# mezzanine.net
KiCad netlist of a schematic drawn in Altium Designer
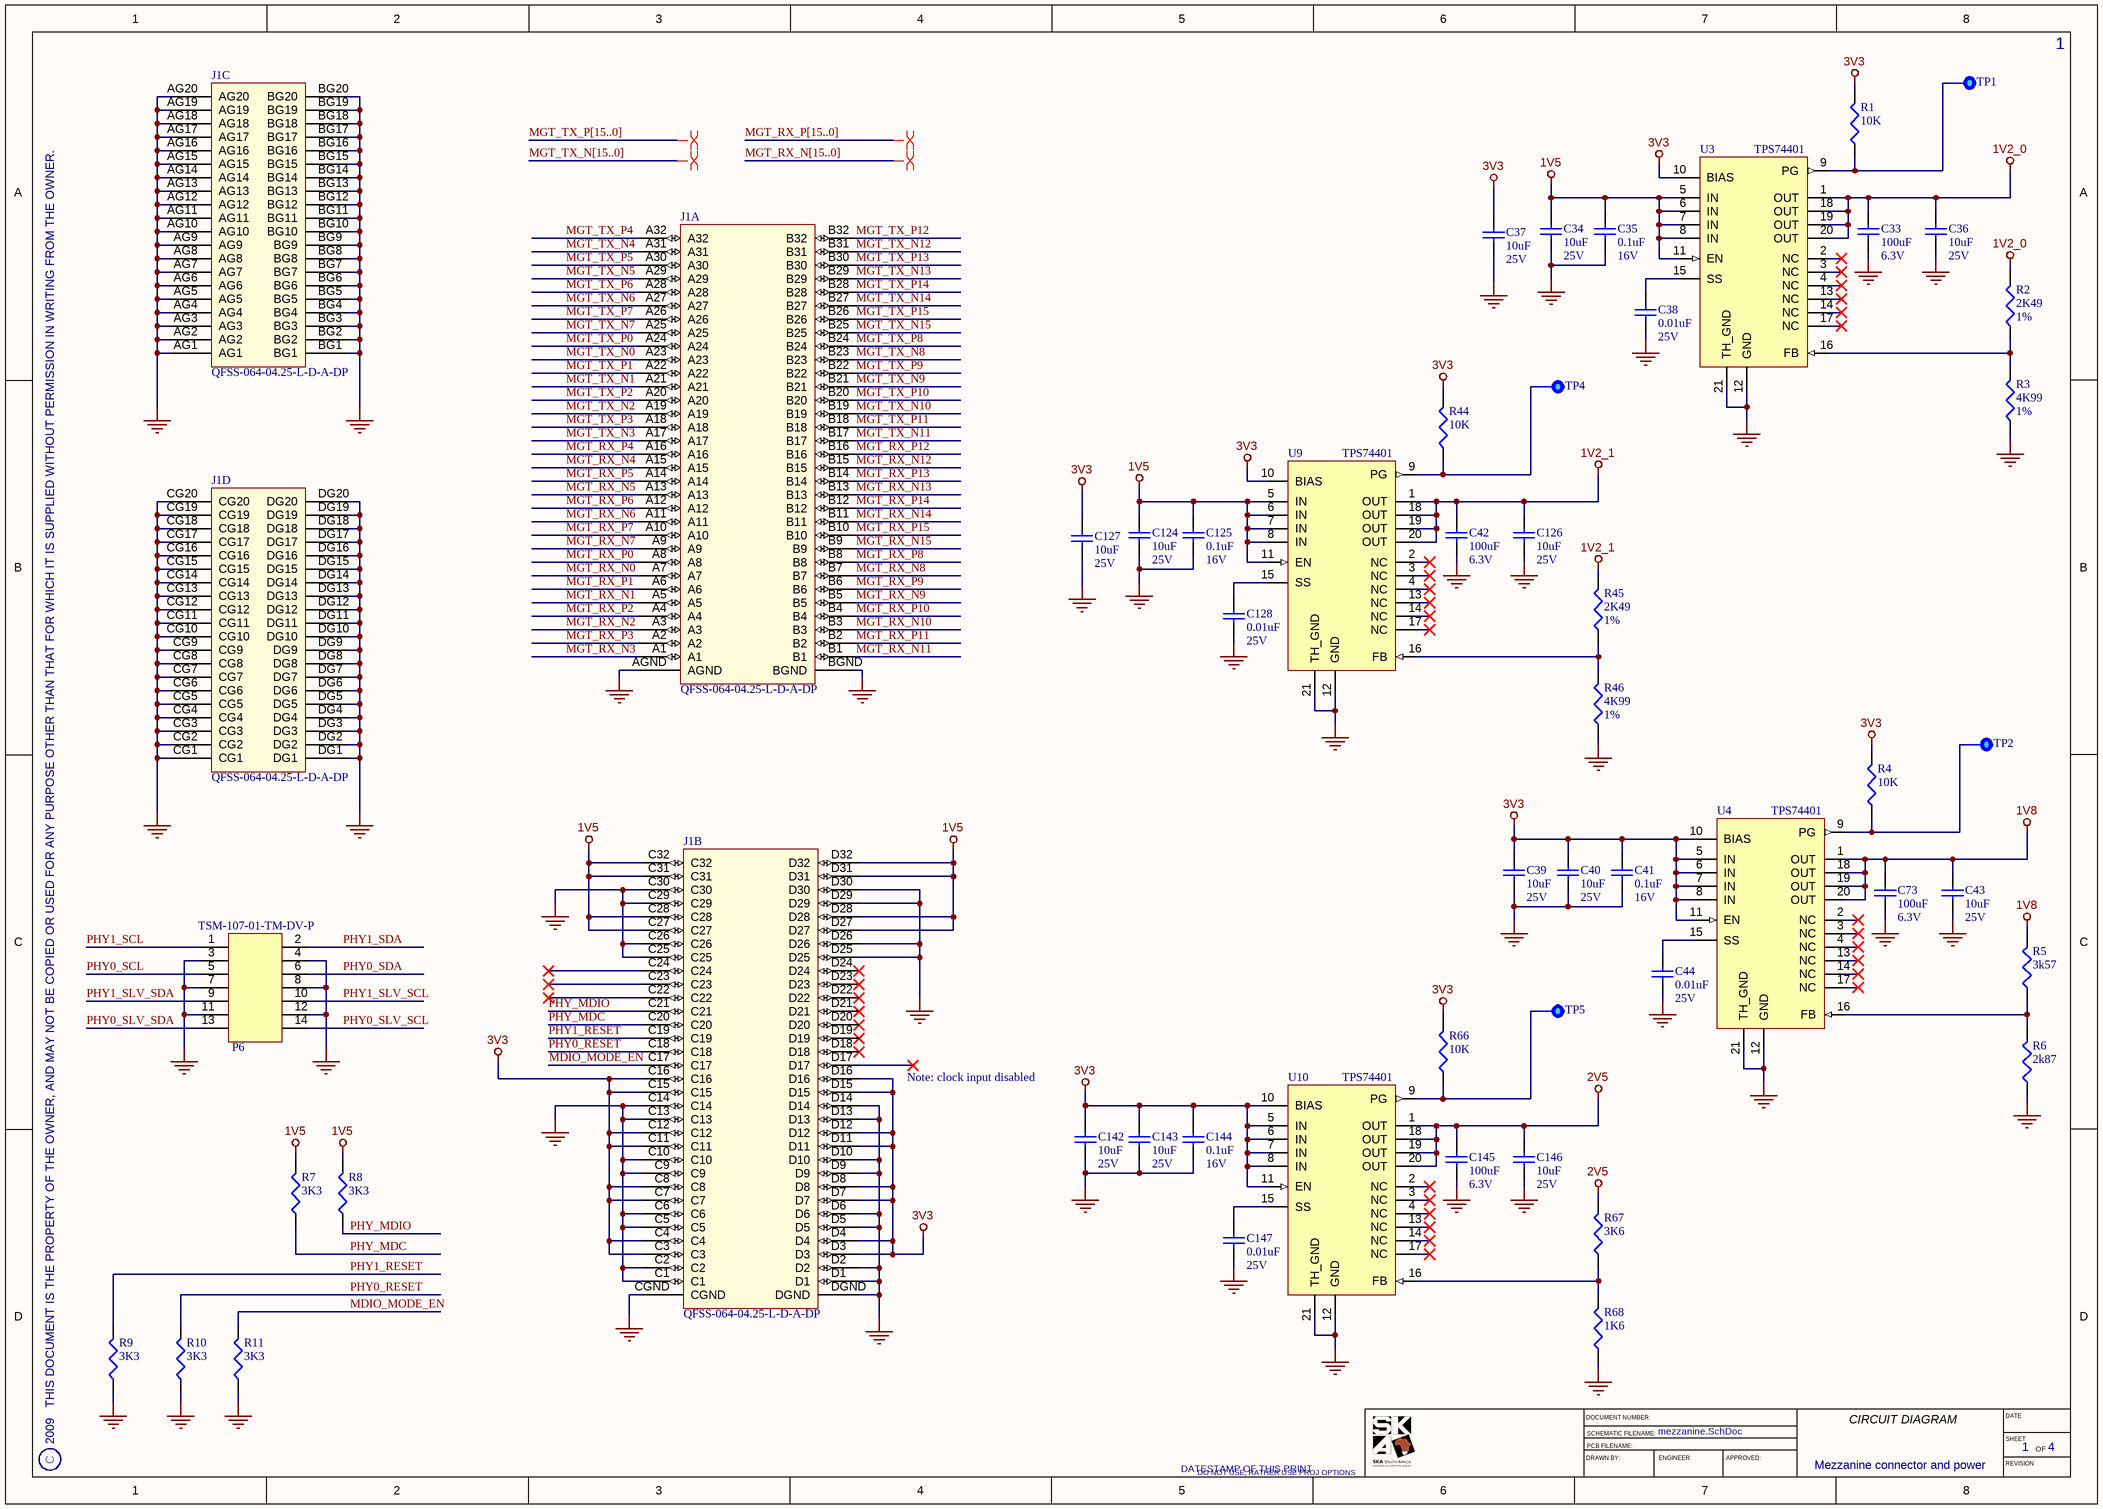
[diagram p0: mezzanine.SchDoc]

(export (version "E")
  (design (tool "Eeschema 10.0.6"))
  (components
    (comp (ref "C33")
      (value "100uF")
      (footprint "CAPC3225X270L")
      (description "100uF, 1210, Ceramic Capacitor")
      (fields
        (field (name "RATING") "6.3V")
        (field (name "MANUFACTURER") "TDK")
        (field (name "PARTNUM") "C3225X5R0J107M")
      )
      (libsource (lib "altium_db") (part "CapStd"))
    )
    (comp (ref "C34")
      (value "10uF")
      (footprint "CAPC3225X200L")
      (description "10uF, Ceramic Capacitor")
      (fields
        (field (name "RATING") "25V")
        (field (name "MANUFACTURER") "MURATA")
        (field (name "PARTNUM") "GRM32DR61E106KA12L")
      )
      (libsource (lib "altium_db") (part "CapStd"))
    )
    (comp (ref "C35")
      (value "0.1uF")
      (footprint "CAPC1005X60L")
      (description "0.1uF, Ceramic Capacitor")
      (fields
        (field (name "RATING") "16V")
        (field (name "MANUFACTURER") "VENKEL")
        (field (name "PARTNUM") "C0402X7R160-104KN")
      )
      (libsource (lib "altium_db") (part "CapStd"))
    )
    (comp (ref "C36")
      (value "10uF")
      (footprint "CAPC3225X200L")
      (description "10uF, Ceramic Capacitor")
      (fields
        (field (name "RATING") "25V")
        (field (name "MANUFACTURER") "MURATA")
        (field (name "PARTNUM") "GRM32DR61E106KA12L")
      )
      (libsource (lib "altium_db") (part "CapStd"))
    )
    (comp (ref "C37")
      (value "10uF")
      (footprint "CAPC3225X200L")
      (description "10uF, Ceramic Capacitor")
      (fields
        (field (name "RATING") "25V")
        (field (name "MANUFACTURER") "MURATA")
        (field (name "PARTNUM") "GRM32DR61E106KA12L")
      )
      (libsource (lib "altium_db") (part "CapStd"))
    )
    (comp (ref "C38")
      (value "0.01uF")
      (footprint "CAPC1005X55L")
      (description "0.01uF, Ceramic Capacitor")
      (fields
        (field (name "RATING") "25V")
        (field (name "MANUFACTURER") "MURATA")
        (field (name "PARTNUM") "GRM155R71E103KA01D")
      )
      (libsource (lib "altium_db") (part "CapStd"))
    )
    (comp (ref "C39")
      (value "10uF")
      (footprint "CAPC3225X200L")
      (description "10uF, Ceramic Capacitor")
      (fields
        (field (name "RATING") "25V")
        (field (name "MANUFACTURER") "MURATA")
        (field (name "PARTNUM") "GRM32DR61E106KA12L")
      )
      (libsource (lib "altium_db") (part "CapStd"))
    )
    (comp (ref "C40")
      (value "10uF")
      (footprint "CAPC3225X200L")
      (description "10uF, Ceramic Capacitor")
      (fields
        (field (name "RATING") "25V")
        (field (name "MANUFACTURER") "MURATA")
        (field (name "PARTNUM") "GRM32DR61E106KA12L")
      )
      (libsource (lib "altium_db") (part "CapStd"))
    )
    (comp (ref "C41")
      (value "0.1uF")
      (footprint "CAPC1005X60L")
      (description "0.1uF, Ceramic Capacitor")
      (fields
        (field (name "RATING") "16V")
        (field (name "MANUFACTURER") "VENKEL")
        (field (name "PARTNUM") "C0402X7R160-104KN")
      )
      (libsource (lib "altium_db") (part "CapStd"))
    )
    (comp (ref "C42")
      (value "100uF")
      (footprint "CAPC3225X270L")
      (description "100uF, 1210, Ceramic Capacitor")
      (fields
        (field (name "RATING") "6.3V")
        (field (name "MANUFACTURER") "TDK")
        (field (name "PARTNUM") "C3225X5R0J107M")
      )
      (libsource (lib "altium_db") (part "CapStd"))
    )
    (comp (ref "C43")
      (value "10uF")
      (footprint "CAPC3225X200L")
      (description "10uF, Ceramic Capacitor")
      (fields
        (field (name "RATING") "25V")
        (field (name "MANUFACTURER") "MURATA")
        (field (name "PARTNUM") "GRM32DR61E106KA12L")
      )
      (libsource (lib "altium_db") (part "CapStd"))
    )
    (comp (ref "C44")
      (value "0.01uF")
      (footprint "CAPC1005X55L")
      (description "0.01uF, Ceramic Capacitor")
      (fields
        (field (name "RATING") "25V")
        (field (name "MANUFACTURER") "MURATA")
        (field (name "PARTNUM") "GRM155R71E103KA01D")
      )
      (libsource (lib "altium_db") (part "CapStd"))
    )
    (comp (ref "C73")
      (value "100uF")
      (footprint "CAPC3225X270L")
      (description "100uF, 1210, Ceramic Capacitor")
      (fields
        (field (name "RATING") "6.3V")
        (field (name "MANUFACTURER") "TDK")
        (field (name "PARTNUM") "C3225X5R0J107M")
      )
      (libsource (lib "altium_db") (part "CapStd"))
    )
    (comp (ref "C124")
      (value "10uF")
      (footprint "CAPC3225X200L")
      (description "10uF, Ceramic Capacitor")
      (fields
        (field (name "RATING") "25V")
        (field (name "MANUFACTURER") "MURATA")
        (field (name "PARTNUM") "GRM32DR61E106KA12L")
      )
      (libsource (lib "altium_db") (part "CapStd"))
    )
    (comp (ref "C125")
      (value "0.1uF")
      (footprint "CAPC1005X60L")
      (description "0.1uF, Ceramic Capacitor")
      (fields
        (field (name "RATING") "16V")
        (field (name "MANUFACTURER") "VENKEL")
        (field (name "PARTNUM") "C0402X7R160-104KN")
      )
      (libsource (lib "altium_db") (part "CapStd"))
    )
    (comp (ref "C126")
      (value "10uF")
      (footprint "CAPC3225X200L")
      (description "10uF, Ceramic Capacitor")
      (fields
        (field (name "RATING") "25V")
        (field (name "MANUFACTURER") "MURATA")
        (field (name "PARTNUM") "GRM32DR61E106KA12L")
      )
      (libsource (lib "altium_db") (part "CapStd"))
    )
    (comp (ref "C127")
      (value "10uF")
      (footprint "CAPC3225X200L")
      (description "10uF, Ceramic Capacitor")
      (fields
        (field (name "RATING") "25V")
        (field (name "MANUFACTURER") "MURATA")
        (field (name "PARTNUM") "GRM32DR61E106KA12L")
      )
      (libsource (lib "altium_db") (part "CapStd"))
    )
    (comp (ref "C128")
      (value "0.01uF")
      (footprint "CAPC1005X55L")
      (description "0.01uF, Ceramic Capacitor")
      (fields
        (field (name "RATING") "25V")
        (field (name "MANUFACTURER") "MURATA")
        (field (name "PARTNUM") "GRM155R71E103KA01D")
      )
      (libsource (lib "altium_db") (part "CapStd"))
    )
    (comp (ref "C142")
      (value "10uF")
      (footprint "CAPC3225X200L")
      (description "10uF, Ceramic Capacitor")
      (fields
        (field (name "RATING") "25V")
        (field (name "MANUFACTURER") "MURATA")
        (field (name "PARTNUM") "GRM32DR61E106KA12L")
      )
      (libsource (lib "altium_db") (part "CapStd"))
    )
    (comp (ref "C143")
      (value "10uF")
      (footprint "CAPC3225X200L")
      (description "10uF, Ceramic Capacitor")
      (fields
        (field (name "RATING") "25V")
        (field (name "MANUFACTURER") "MURATA")
        (field (name "PARTNUM") "GRM32DR61E106KA12L")
      )
      (libsource (lib "altium_db") (part "CapStd"))
    )
    (comp (ref "C144")
      (value "0.1uF")
      (footprint "CAPC1005X60L")
      (description "0.1uF, Ceramic Capacitor")
      (fields
        (field (name "RATING") "16V")
        (field (name "MANUFACTURER") "VENKEL")
        (field (name "PARTNUM") "C0402X7R160-104KN")
      )
      (libsource (lib "altium_db") (part "CapStd"))
    )
    (comp (ref "C145")
      (value "100uF")
      (footprint "CAPC3225X270L")
      (description "100uF, 1210, Ceramic Capacitor")
      (fields
        (field (name "RATING") "6.3V")
        (field (name "MANUFACTURER") "TDK")
        (field (name "PARTNUM") "C3225X5R0J107M")
      )
      (libsource (lib "altium_db") (part "CapStd"))
    )
    (comp (ref "C146")
      (value "10uF")
      (footprint "CAPC3225X200L")
      (description "10uF, Ceramic Capacitor")
      (fields
        (field (name "RATING") "25V")
        (field (name "MANUFACTURER") "MURATA")
        (field (name "PARTNUM") "GRM32DR61E106KA12L")
      )
      (libsource (lib "altium_db") (part "CapStd"))
    )
    (comp (ref "C147")
      (value "0.01uF")
      (footprint "CAPC1005X55L")
      (description "0.01uF, Ceramic Capacitor")
      (fields
        (field (name "RATING") "25V")
        (field (name "MANUFACTURER") "MURATA")
        (field (name "PARTNUM") "GRM155R71E103KA01D")
      )
      (libsource (lib "altium_db") (part "CapStd"))
    )
    (comp (ref "J1")
      (value "QFSS-064-04.25-L-D-A-DP")
      (footprint "SAMTEC_QFSS-064-04.25-L-D-DP-A")
      (description "Shielded, 64-Differential Pair, Rugged High-Speed Terminal Strip, 0.635mm Pitch")
      (fields (field (name "PARTNUM") "QFSS-064-04.25-L-D-A-DP") (field (name "MANUFACTURER") "SAMTEC"))
      (libsource (lib "altium_db") (part "QFSS-064-04.25-L-D-A-DP"))
    )
    (comp (ref "P6")
      (value "TSM-107-01-TM-DV-P")
      (footprint "SAMTEC_TSM-107-01-TM-DV-P")
      (description "2x7, 2.54 mm Pitch, Male Header")
      (fields (field (name "PARTNUM") "TSM-107-01-TM-DV-P") (field (name "MANUFACTURER") "SAMTEC"))
      (libsource (lib "altium_db") (part "con_hdr_2x7"))
    )
    (comp (ref "R1")
      (value "10K")
      (footprint "RESC1005X40L")
      (description "10K, 1.1mm x 0.5mm, Thick Film Resistor")
      (fields (field (name "MANUFACTURER") "ROYALOHM") (field (name "PARTNUM") "0402WGJ0103T1E"))
      (libsource (lib "altium_db") (part "ResStd"))
    )
    (comp (ref "R2")
      (value "2K49")
      (footprint "RESC1005X40L")
      (description "2K49, 1.1mm x 0.5mm, Thick Film Resistor")
      (fields
        (field (name "MANUFACTURER") "ROYALOHM")
        (field (name "PARTNUM") "0402WGF2K49T1E")
        (field (name "TOLERANCE") "1%")
      )
      (libsource (lib "altium_db") (part "ResStd"))
    )
    (comp (ref "R3")
      (value "4K99")
      (footprint "RESC1005X40L")
      (description "4K99, 1.1mm x 0.5mm, Thick Film Resistor")
      (fields
        (field (name "MANUFACTURER") "ROYALOHM")
        (field (name "PARTNUM") "0402WGF4991T1E")
        (field (name "TOLERANCE") "1%")
      )
      (libsource (lib "altium_db") (part "ResStd"))
    )
    (comp (ref "R4")
      (value "10K")
      (footprint "RESC1005X40L")
      (description "10K, 1.1mm x 0.5mm, Thick Film Resistor")
      (fields (field (name "MANUFACTURER") "ROYALOHM") (field (name "PARTNUM") "0402WGJ0103T1E"))
      (libsource (lib "altium_db") (part "ResStd"))
    )
    (comp (ref "R5")
      (value "3k57")
      (footprint "RESC1005X40L")
      (description "3K57, 1.1mm x 0.5mm, Thick Film Resistor")
      (fields (field (name "MANUFACTURER") "STACKPOLE") (field (name "PARTNUM") "RMC0402FT3K57"))
      (libsource (lib "altium_db") (part "ResStd"))
    )
    (comp (ref "R6")
      (value "2k87")
      (footprint "RESC1005X40L")
      (description "2K87, 1.1mm x 0.5mm, Thick Film Resistor")
      (fields (field (name "MANUFACTURER") "STACKPOLE") (field (name "PARTNUM") "RMC0402FT2K87"))
      (libsource (lib "altium_db") (part "ResStd"))
    )
    (comp (ref "R7")
      (value "3K3")
      (footprint "RESC1005X40L")
      (description "3K3, 1.1mm x 0.5mm, Thick Film Resistor")
      (fields (field (name "MANUFACTURER") "ROYALOHM") (field (name "PARTNUM") "0402WGJ0332T1E"))
      (libsource (lib "altium_db") (part "ResStd"))
    )
    (comp (ref "R8")
      (value "3K3")
      (footprint "RESC1005X40L")
      (description "3K3, 1.1mm x 0.5mm, Thick Film Resistor")
      (fields (field (name "MANUFACTURER") "ROYALOHM") (field (name "PARTNUM") "0402WGJ0332T1E"))
      (libsource (lib "altium_db") (part "ResStd"))
    )
    (comp (ref "R9")
      (value "3K3")
      (footprint "RESC1005X40L")
      (description "3K3, 1.1mm x 0.5mm, Thick Film Resistor")
      (fields (field (name "MANUFACTURER") "ROYALOHM") (field (name "PARTNUM") "0402WGJ0332T1E"))
      (libsource (lib "altium_db") (part "ResStd"))
    )
    (comp (ref "R10")
      (value "3K3")
      (footprint "RESC1005X40L")
      (description "3K3, 1.1mm x 0.5mm, Thick Film Resistor")
      (fields (field (name "MANUFACTURER") "ROYALOHM") (field (name "PARTNUM") "0402WGJ0332T1E"))
      (libsource (lib "altium_db") (part "ResStd"))
    )
    (comp (ref "R11")
      (value "3K3")
      (footprint "RESC1005X40L")
      (description "3K3, 1.1mm x 0.5mm, Thick Film Resistor")
      (fields (field (name "MANUFACTURER") "ROYALOHM") (field (name "PARTNUM") "0402WGJ0332T1E"))
      (libsource (lib "altium_db") (part "ResStd"))
    )
    (comp (ref "R44")
      (value "10K")
      (footprint "RESC1005X40L")
      (description "10K, 1.1mm x 0.5mm, Thick Film Resistor")
      (fields (field (name "MANUFACTURER") "ROYALOHM") (field (name "PARTNUM") "0402WGJ0103T1E"))
      (libsource (lib "altium_db") (part "ResStd"))
    )
    (comp (ref "R45")
      (value "2K49")
      (footprint "RESC1005X40L")
      (description "2K49, 1.1mm x 0.5mm, Thick Film Resistor")
      (fields
        (field (name "MANUFACTURER") "ROYALOHM")
        (field (name "PARTNUM") "0402WGF2K49T1E")
        (field (name "TOLERANCE") "1%")
      )
      (libsource (lib "altium_db") (part "ResStd"))
    )
    (comp (ref "R46")
      (value "4K99")
      (footprint "RESC1005X40L")
      (description "4K99, 1.1mm x 0.5mm, Thick Film Resistor")
      (fields
        (field (name "MANUFACTURER") "ROYALOHM")
        (field (name "PARTNUM") "0402WGF4991T1E")
        (field (name "TOLERANCE") "1%")
      )
      (libsource (lib "altium_db") (part "ResStd"))
    )
    (comp (ref "R66")
      (value "10K")
      (footprint "RESC1005X40L")
      (description "10K, 1.1mm x 0.5mm, Thick Film Resistor")
      (fields (field (name "MANUFACTURER") "ROYALOHM") (field (name "PARTNUM") "0402WGJ0103T1E"))
      (libsource (lib "altium_db") (part "ResStd"))
    )
    (comp (ref "R67")
      (value "3K6")
      (footprint "RESC1005X40L")
      (description "3K6, 1.1mm x 0.5mm, Thick Film Resistor")
      (fields (field (name "MANUFACTURER") "ROYALOHM") (field (name "PARTNUM") "0402WGF3601T1E"))
      (libsource (lib "Altium_DB") (part "ResStd"))
    )
    (comp (ref "R68")
      (value "1K6")
      (footprint "RESC1005X40L")
      (description "1K6, 1.1mm x 0.5mm, Thick Film Resistor")
      (fields (field (name "MANUFACTURER") "ROYALOHM") (field (name "PARTNUM") "0402WGF1601T1E"))
      (libsource (lib "Altium_DB") (part "ResStd"))
    )
    (comp (ref "TP1")
      (value "Testpoint")
      (footprint "TP100")
      (description "1mm Diameter, through-hole, Circular Test-point")
      (libsource (lib "altium_db") (part "Testpoint"))
    )
    (comp (ref "TP2")
      (value "Testpoint")
      (footprint "TP100")
      (description "1mm Diameter, through-hole, Circular Test-point")
      (libsource (lib "altium_db") (part "Testpoint"))
    )
    (comp (ref "TP4")
      (value "Testpoint")
      (footprint "TP100")
      (description "1mm Diameter, through-hole, Circular Test-point")
      (libsource (lib "altium_db") (part "Testpoint"))
    )
    (comp (ref "TP5")
      (value "Testpoint")
      (footprint "TP100")
      (description "1mm Diameter, through-hole, Circular Test-point")
      (libsource (lib "altium_db") (part "Testpoint"))
    )
    (comp (ref "U3")
      (value "TPS74401")
      (footprint "VQFN20")
      (description "3.0A Ultra-LDO with Programmable Soft-Start")
      (fields (field (name "MANUFACTURER") "Texas Instruments"))
      (libsource (lib "altium_db") (part "TPS74401"))
    )
    (comp (ref "U4")
      (value "TPS74401")
      (footprint "VQFN20")
      (description "3.0A Ultra-LDO with Programmable Soft-Start")
      (fields (field (name "MANUFACTURER") "Texas Instruments"))
      (libsource (lib "altium_db") (part "TPS74401"))
    )
    (comp (ref "U9")
      (value "TPS74401")
      (footprint "VQFN20")
      (description "3.0A Ultra-LDO with Programmable Soft-Start")
      (fields (field (name "MANUFACTURER") "Texas Instruments"))
      (libsource (lib "altium_db") (part "TPS74401"))
    )
    (comp (ref "U10")
      (value "TPS74401")
      (footprint "VQFN20")
      (description "3.0A Ultra-LDO with Programmable Soft-Start")
      (fields (field (name "MANUFACTURER") "Texas Instruments"))
      (libsource (lib "altium_db") (part "TPS74401"))
    )
  )
  (nets
    (net (code "1") (name "/MDIO_MODE_EN") (class "Default")
      (node (ref "J1") (pin "C17") (pinfunction "C17_C17") (pintype "bidirectional"))
      (node (ref "R11") (pin "2") (pinfunction "2_2") (pintype "passive"))
    )
    (net (code "2") (name "/MGT_RX_N0") (class "Default")
      (node (ref "J1") (pin "A7") (pinfunction "A7_A7") (pintype "bidirectional"))
    )
    (net (code "3") (name "/MGT_RX_N1") (class "Default")
      (node (ref "J1") (pin "A5") (pinfunction "A5_A5") (pintype "bidirectional"))
    )
    (net (code "4") (name "/MGT_RX_N2") (class "Default")
      (node (ref "J1") (pin "A3") (pinfunction "A3_A3") (pintype "bidirectional"))
    )
    (net (code "5") (name "/MGT_RX_N3") (class "Default")
      (node (ref "J1") (pin "A1") (pinfunction "A1_A1") (pintype "bidirectional"))
    )
    (net (code "6") (name "/MGT_RX_N4") (class "Default")
      (node (ref "J1") (pin "A15") (pinfunction "A15_A15") (pintype "bidirectional"))
    )
    (net (code "7") (name "/MGT_RX_N5") (class "Default")
      (node (ref "J1") (pin "A13") (pinfunction "A13_A13") (pintype "bidirectional"))
    )
    (net (code "8") (name "/MGT_RX_N6") (class "Default")
      (node (ref "J1") (pin "A11") (pinfunction "A11_A11") (pintype "bidirectional"))
    )
    (net (code "9") (name "/MGT_RX_N7") (class "Default")
      (node (ref "J1") (pin "A9") (pinfunction "A9_A9") (pintype "bidirectional"))
    )
    (net (code "10") (name "/MGT_RX_N8") (class "Default")
      (node (ref "J1") (pin "B7") (pinfunction "B7_B7") (pintype "bidirectional"))
    )
    (net (code "11") (name "/MGT_RX_N9") (class "Default")
      (node (ref "J1") (pin "B5") (pinfunction "B5_B5") (pintype "bidirectional"))
    )
    (net (code "12") (name "/MGT_RX_N10") (class "Default")
      (node (ref "J1") (pin "B3") (pinfunction "B3_B3") (pintype "bidirectional"))
    )
    (net (code "13") (name "/MGT_RX_N11") (class "Default")
      (node (ref "J1") (pin "B1") (pinfunction "B1_B1") (pintype "bidirectional"))
    )
    (net (code "14") (name "/MGT_RX_N12") (class "Default")
      (node (ref "J1") (pin "B15") (pinfunction "B15_B15") (pintype "bidirectional"))
    )
    (net (code "15") (name "/MGT_RX_N13") (class "Default")
      (node (ref "J1") (pin "B13") (pinfunction "B13_B13") (pintype "bidirectional"))
    )
    (net (code "16") (name "/MGT_RX_N14") (class "Default")
      (node (ref "J1") (pin "B11") (pinfunction "B11_B11") (pintype "bidirectional"))
    )
    (net (code "17") (name "/MGT_RX_N15") (class "Default")
      (node (ref "J1") (pin "B9") (pinfunction "B9_B9") (pintype "bidirectional"))
    )
    (net (code "19") (name "/MGT_RX_P0") (class "Default")
      (node (ref "J1") (pin "A8") (pinfunction "A8_A8") (pintype "bidirectional"))
    )
    (net (code "20") (name "/MGT_RX_P1") (class "Default")
      (node (ref "J1") (pin "A6") (pinfunction "A6_A6") (pintype "bidirectional"))
    )
    (net (code "21") (name "/MGT_RX_P2") (class "Default")
      (node (ref "J1") (pin "A4") (pinfunction "A4_A4") (pintype "bidirectional"))
    )
    (net (code "22") (name "/MGT_RX_P3") (class "Default")
      (node (ref "J1") (pin "A2") (pinfunction "A2_A2") (pintype "bidirectional"))
    )
    (net (code "23") (name "/MGT_RX_P4") (class "Default")
      (node (ref "J1") (pin "A16") (pinfunction "A16_A16") (pintype "bidirectional"))
    )
    (net (code "24") (name "/MGT_RX_P5") (class "Default")
      (node (ref "J1") (pin "A14") (pinfunction "A14_A14") (pintype "bidirectional"))
    )
    (net (code "25") (name "/MGT_RX_P6") (class "Default")
      (node (ref "J1") (pin "A12") (pinfunction "A12_A12") (pintype "bidirectional"))
    )
    (net (code "26") (name "/MGT_RX_P7") (class "Default")
      (node (ref "J1") (pin "A10") (pinfunction "A10_A10") (pintype "bidirectional"))
    )
    (net (code "27") (name "/MGT_RX_P8") (class "Default")
      (node (ref "J1") (pin "B8") (pinfunction "B8_B8") (pintype "bidirectional"))
    )
    (net (code "28") (name "/MGT_RX_P9") (class "Default")
      (node (ref "J1") (pin "B6") (pinfunction "B6_B6") (pintype "bidirectional"))
    )
    (net (code "29") (name "/MGT_RX_P10") (class "Default")
      (node (ref "J1") (pin "B4") (pinfunction "B4_B4") (pintype "bidirectional"))
    )
    (net (code "30") (name "/MGT_RX_P11") (class "Default")
      (node (ref "J1") (pin "B2") (pinfunction "B2_B2") (pintype "bidirectional"))
    )
    (net (code "31") (name "/MGT_RX_P12") (class "Default")
      (node (ref "J1") (pin "B16") (pinfunction "B16_B16") (pintype "bidirectional"))
    )
    (net (code "32") (name "/MGT_RX_P13") (class "Default")
      (node (ref "J1") (pin "B14") (pinfunction "B14_B14") (pintype "bidirectional"))
    )
    (net (code "33") (name "/MGT_RX_P14") (class "Default")
      (node (ref "J1") (pin "B12") (pinfunction "B12_B12") (pintype "bidirectional"))
    )
    (net (code "34") (name "/MGT_RX_P15") (class "Default")
      (node (ref "J1") (pin "B10") (pinfunction "B10_B10") (pintype "bidirectional"))
    )
    (net (code "36") (name "/MGT_TX_N0") (class "Default")
      (node (ref "J1") (pin "A23") (pinfunction "A23_A23") (pintype "bidirectional"))
    )
    (net (code "37") (name "/MGT_TX_N1") (class "Default")
      (node (ref "J1") (pin "A21") (pinfunction "A21_A21") (pintype "bidirectional"))
    )
    (net (code "38") (name "/MGT_TX_N2") (class "Default")
      (node (ref "J1") (pin "A19") (pinfunction "A19_A19") (pintype "bidirectional"))
    )
    (net (code "39") (name "/MGT_TX_N3") (class "Default")
      (node (ref "J1") (pin "A17") (pinfunction "A17_A17") (pintype "bidirectional"))
    )
    (net (code "40") (name "/MGT_TX_N4") (class "Default")
      (node (ref "J1") (pin "A31") (pinfunction "A31_A31") (pintype "bidirectional"))
    )
    (net (code "41") (name "/MGT_TX_N5") (class "Default")
      (node (ref "J1") (pin "A29") (pinfunction "A29_A29") (pintype "bidirectional"))
    )
    (net (code "42") (name "/MGT_TX_N6") (class "Default")
      (node (ref "J1") (pin "A27") (pinfunction "A27_A27") (pintype "bidirectional"))
    )
    (net (code "43") (name "/MGT_TX_N7") (class "Default")
      (node (ref "J1") (pin "A25") (pinfunction "A25_A25") (pintype "bidirectional"))
    )
    (net (code "44") (name "/MGT_TX_N8") (class "Default")
      (node (ref "J1") (pin "B23") (pinfunction "B23_B23") (pintype "bidirectional"))
    )
    (net (code "45") (name "/MGT_TX_N9") (class "Default")
      (node (ref "J1") (pin "B21") (pinfunction "B21_B21") (pintype "bidirectional"))
    )
    (net (code "46") (name "/MGT_TX_N10") (class "Default")
      (node (ref "J1") (pin "B19") (pinfunction "B19_B19") (pintype "bidirectional"))
    )
    (net (code "47") (name "/MGT_TX_N11") (class "Default")
      (node (ref "J1") (pin "B17") (pinfunction "B17_B17") (pintype "bidirectional"))
    )
    (net (code "48") (name "/MGT_TX_N12") (class "Default")
      (node (ref "J1") (pin "B31") (pinfunction "B31_B31") (pintype "bidirectional"))
    )
    (net (code "49") (name "/MGT_TX_N13") (class "Default")
      (node (ref "J1") (pin "B29") (pinfunction "B29_B29") (pintype "bidirectional"))
    )
    (net (code "50") (name "/MGT_TX_N14") (class "Default")
      (node (ref "J1") (pin "B27") (pinfunction "B27_B27") (pintype "bidirectional"))
    )
    (net (code "51") (name "/MGT_TX_N15") (class "Default")
      (node (ref "J1") (pin "B25") (pinfunction "B25_B25") (pintype "bidirectional"))
    )
    (net (code "53") (name "/MGT_TX_P0") (class "Default")
      (node (ref "J1") (pin "A24") (pinfunction "A24_A24") (pintype "bidirectional"))
    )
    (net (code "54") (name "/MGT_TX_P1") (class "Default")
      (node (ref "J1") (pin "A22") (pinfunction "A22_A22") (pintype "bidirectional"))
    )
    (net (code "55") (name "/MGT_TX_P2") (class "Default")
      (node (ref "J1") (pin "A20") (pinfunction "A20_A20") (pintype "bidirectional"))
    )
    (net (code "56") (name "/MGT_TX_P3") (class "Default")
      (node (ref "J1") (pin "A18") (pinfunction "A18_A18") (pintype "bidirectional"))
    )
    (net (code "57") (name "/MGT_TX_P4") (class "Default")
      (node (ref "J1") (pin "A32") (pinfunction "A32_A32") (pintype "bidirectional"))
    )
    (net (code "58") (name "/MGT_TX_P5") (class "Default")
      (node (ref "J1") (pin "A30") (pinfunction "A30_A30") (pintype "bidirectional"))
    )
    (net (code "59") (name "/MGT_TX_P6") (class "Default")
      (node (ref "J1") (pin "A28") (pinfunction "A28_A28") (pintype "bidirectional"))
    )
    (net (code "60") (name "/MGT_TX_P7") (class "Default")
      (node (ref "J1") (pin "A26") (pinfunction "A26_A26") (pintype "bidirectional"))
    )
    (net (code "61") (name "/MGT_TX_P8") (class "Default")
      (node (ref "J1") (pin "B24") (pinfunction "B24_B24") (pintype "bidirectional"))
    )
    (net (code "62") (name "/MGT_TX_P9") (class "Default")
      (node (ref "J1") (pin "B22") (pinfunction "B22_B22") (pintype "bidirectional"))
    )
    (net (code "63") (name "/MGT_TX_P10") (class "Default")
      (node (ref "J1") (pin "B20") (pinfunction "B20_B20") (pintype "bidirectional"))
    )
    (net (code "64") (name "/MGT_TX_P11") (class "Default")
      (node (ref "J1") (pin "B18") (pinfunction "B18_B18") (pintype "bidirectional"))
    )
    (net (code "65") (name "/MGT_TX_P12") (class "Default")
      (node (ref "J1") (pin "B32") (pinfunction "B32_B32") (pintype "bidirectional"))
    )
    (net (code "66") (name "/MGT_TX_P13") (class "Default")
      (node (ref "J1") (pin "B30") (pinfunction "B30_B30") (pintype "bidirectional"))
    )
    (net (code "67") (name "/MGT_TX_P14") (class "Default")
      (node (ref "J1") (pin "B28") (pinfunction "B28_B28") (pintype "bidirectional"))
    )
    (net (code "68") (name "/MGT_TX_P15") (class "Default")
      (node (ref "J1") (pin "B26") (pinfunction "B26_B26") (pintype "bidirectional"))
    )
    (net (code "70") (name "/PHY0_RESET") (class "Default")
      (node (ref "J1") (pin "C18") (pinfunction "C18_C18") (pintype "bidirectional"))
      (node (ref "R10") (pin "2") (pinfunction "2_2") (pintype "passive"))
    )
    (net (code "71") (name "/PHY0_SCL") (class "Default")
      (node (ref "P6") (pin "5") (pinfunction "5_5") (pintype "passive"))
    )
    (net (code "72") (name "/PHY0_SDA") (class "Default")
      (node (ref "P6") (pin "6") (pinfunction "6_6") (pintype "passive"))
    )
    (net (code "73") (name "/PHY0_SLV_SCL") (class "Default")
      (node (ref "P6") (pin "14") (pinfunction "14_14") (pintype "passive"))
    )
    (net (code "74") (name "/PHY0_SLV_SDA") (class "Default")
      (node (ref "P6") (pin "13") (pinfunction "13_13") (pintype "passive"))
    )
    (net (code "75") (name "/PHY1_RESET") (class "Default")
      (node (ref "J1") (pin "C19") (pinfunction "C19_C19") (pintype "bidirectional"))
      (node (ref "R9") (pin "2") (pinfunction "2_2") (pintype "passive"))
    )
    (net (code "76") (name "/PHY1_SCL") (class "Default")
      (node (ref "P6") (pin "1") (pinfunction "1_1") (pintype "passive"))
    )
    (net (code "77") (name "/PHY1_SDA") (class "Default")
      (node (ref "P6") (pin "2") (pinfunction "2_2") (pintype "passive"))
    )
    (net (code "78") (name "/PHY1_SLV_SCL") (class "Default")
      (node (ref "P6") (pin "10") (pinfunction "10_10") (pintype "passive"))
    )
    (net (code "79") (name "/PHY1_SLV_SDA") (class "Default")
      (node (ref "P6") (pin "9") (pinfunction "9_9") (pintype "passive"))
    )
    (net (code "80") (name "/PHY_MDC") (class "Default")
      (node (ref "J1") (pin "C20") (pinfunction "C20_C20") (pintype "bidirectional"))
      (node (ref "R7") (pin "1") (pinfunction "1_1") (pintype "passive"))
    )
    (net (code "81") (name "/PHY_MDIO") (class "Default")
      (node (ref "J1") (pin "C21") (pinfunction "C21_C21") (pintype "bidirectional"))
      (node (ref "R8") (pin "1") (pinfunction "1_1") (pintype "passive"))
    )
    (net (code "82") (name "1V2_0") (class "Default")
      (node (ref "C33") (pin "2") (pinfunction "2_2") (pintype "passive"))
      (node (ref "C36") (pin "2") (pinfunction "2_2") (pintype "passive"))
      (node (ref "R2") (pin "2") (pinfunction "2_2") (pintype "passive"))
      (node (ref "U3") (pin "1") (pinfunction "OUT_1") (pintype "power_in"))
      (node (ref "U3") (pin "18") (pinfunction "OUT_18") (pintype "power_in"))
      (node (ref "U3") (pin "19") (pinfunction "OUT_19") (pintype "power_in"))
      (node (ref "U3") (pin "20") (pinfunction "OUT_20") (pintype "power_in"))
    )
    (net (code "83") (name "1V2_1") (class "Default")
      (node (ref "C126") (pin "2") (pinfunction "2_2") (pintype "passive"))
      (node (ref "C42") (pin "2") (pinfunction "2_2") (pintype "passive"))
      (node (ref "R45") (pin "2") (pinfunction "2_2") (pintype "passive"))
      (node (ref "U9") (pin "1") (pinfunction "OUT_1") (pintype "power_in"))
      (node (ref "U9") (pin "18") (pinfunction "OUT_18") (pintype "power_in"))
      (node (ref "U9") (pin "19") (pinfunction "OUT_19") (pintype "power_in"))
      (node (ref "U9") (pin "20") (pinfunction "OUT_20") (pintype "power_in"))
    )
    (net (code "84") (name "1V5") (class "Default")
      (node (ref "C124") (pin "2") (pinfunction "2_2") (pintype "passive"))
      (node (ref "C125") (pin "2") (pinfunction "2_2") (pintype "passive"))
      (node (ref "C34") (pin "2") (pinfunction "2_2") (pintype "passive"))
      (node (ref "C35") (pin "2") (pinfunction "2_2") (pintype "passive"))
      (node (ref "J1") (pin "C27") (pinfunction "C27_C27") (pintype "bidirectional"))
      (node (ref "J1") (pin "C28") (pinfunction "C28_C28") (pintype "bidirectional"))
      (node (ref "J1") (pin "C31") (pinfunction "C31_C31") (pintype "bidirectional"))
      (node (ref "J1") (pin "C32") (pinfunction "C32_C32") (pintype "bidirectional"))
      (node (ref "J1") (pin "D27") (pinfunction "D27_D27") (pintype "bidirectional"))
      (node (ref "J1") (pin "D28") (pinfunction "D28_D28") (pintype "bidirectional"))
      (node (ref "J1") (pin "D31") (pinfunction "D31_D31") (pintype "bidirectional"))
      (node (ref "J1") (pin "D32") (pinfunction "D32_D32") (pintype "bidirectional"))
      (node (ref "R7") (pin "2") (pinfunction "2_2") (pintype "passive"))
      (node (ref "R8") (pin "2") (pinfunction "2_2") (pintype "passive"))
      (node (ref "U3") (pin "11") (pinfunction "EN_11") (pintype "input"))
      (node (ref "U3") (pin "5") (pinfunction "IN_5") (pintype "power_in"))
      (node (ref "U3") (pin "6") (pinfunction "IN_6") (pintype "power_in"))
      (node (ref "U3") (pin "7") (pinfunction "IN_7") (pintype "power_in"))
      (node (ref "U3") (pin "8") (pinfunction "IN_8") (pintype "power_in"))
      (node (ref "U9") (pin "11") (pinfunction "EN_11") (pintype "input"))
      (node (ref "U9") (pin "5") (pinfunction "IN_5") (pintype "power_in"))
      (node (ref "U9") (pin "6") (pinfunction "IN_6") (pintype "power_in"))
      (node (ref "U9") (pin "7") (pinfunction "IN_7") (pintype "power_in"))
      (node (ref "U9") (pin "8") (pinfunction "IN_8") (pintype "power_in"))
    )
    (net (code "85") (name "1V8") (class "Default")
      (node (ref "C43") (pin "2") (pinfunction "2_2") (pintype "passive"))
      (node (ref "C73") (pin "2") (pinfunction "2_2") (pintype "passive"))
      (node (ref "R5") (pin "2") (pinfunction "2_2") (pintype "passive"))
      (node (ref "U4") (pin "1") (pinfunction "OUT_1") (pintype "power_in"))
      (node (ref "U4") (pin "18") (pinfunction "OUT_18") (pintype "power_in"))
      (node (ref "U4") (pin "19") (pinfunction "OUT_19") (pintype "power_in"))
      (node (ref "U4") (pin "20") (pinfunction "OUT_20") (pintype "power_in"))
    )
    (net (code "86") (name "2V5") (class "Default")
      (node (ref "C145") (pin "2") (pinfunction "2_2") (pintype "passive"))
      (node (ref "C146") (pin "2") (pinfunction "2_2") (pintype "passive"))
      (node (ref "R67") (pin "2") (pinfunction "2_2") (pintype "passive"))
      (node (ref "U10") (pin "1") (pinfunction "OUT_1") (pintype "power_in"))
      (node (ref "U10") (pin "18") (pinfunction "OUT_18") (pintype "power_in"))
      (node (ref "U10") (pin "19") (pinfunction "OUT_19") (pintype "power_in"))
      (node (ref "U10") (pin "20") (pinfunction "OUT_20") (pintype "power_in"))
    )
    (net (code "87") (name "3V3") (class "Default")
      (node (ref "C127") (pin "2") (pinfunction "2_2") (pintype "passive"))
      (node (ref "C142") (pin "2") (pinfunction "2_2") (pintype "passive"))
      (node (ref "C143") (pin "2") (pinfunction "2_2") (pintype "passive"))
      (node (ref "C144") (pin "2") (pinfunction "2_2") (pintype "passive"))
      (node (ref "C37") (pin "2") (pinfunction "2_2") (pintype "passive"))
      (node (ref "C39") (pin "2") (pinfunction "2_2") (pintype "passive"))
      (node (ref "C40") (pin "2") (pinfunction "2_2") (pintype "passive"))
      (node (ref "C41") (pin "2") (pinfunction "2_2") (pintype "passive"))
      (node (ref "J1") (pin "C11") (pinfunction "C11_C11") (pintype "bidirectional"))
      (node (ref "J1") (pin "C12") (pinfunction "C12_C12") (pintype "bidirectional"))
      (node (ref "J1") (pin "C15") (pinfunction "C15_C15") (pintype "bidirectional"))
      (node (ref "J1") (pin "C16") (pinfunction "C16_C16") (pintype "bidirectional"))
      (node (ref "J1") (pin "C3") (pinfunction "C3_C3") (pintype "bidirectional"))
      (node (ref "J1") (pin "C4") (pinfunction "C4_C4") (pintype "bidirectional"))
      (node (ref "J1") (pin "C7") (pinfunction "C7_C7") (pintype "bidirectional"))
      (node (ref "J1") (pin "C8") (pinfunction "C8_C8") (pintype "bidirectional"))
      (node (ref "J1") (pin "D11") (pinfunction "D11_D11") (pintype "bidirectional"))
      (node (ref "J1") (pin "D12") (pinfunction "D12_D12") (pintype "bidirectional"))
      (node (ref "J1") (pin "D15") (pinfunction "D15_D15") (pintype "bidirectional"))
      (node (ref "J1") (pin "D16") (pinfunction "D16_D16") (pintype "bidirectional"))
      (node (ref "J1") (pin "D3") (pinfunction "D3_D3") (pintype "bidirectional"))
      (node (ref "J1") (pin "D4") (pinfunction "D4_D4") (pintype "bidirectional"))
      (node (ref "J1") (pin "D7") (pinfunction "D7_D7") (pintype "bidirectional"))
      (node (ref "J1") (pin "D8") (pinfunction "D8_D8") (pintype "bidirectional"))
      (node (ref "R1") (pin "2") (pinfunction "2_2") (pintype "passive"))
      (node (ref "R4") (pin "2") (pinfunction "2_2") (pintype "passive"))
      (node (ref "R44") (pin "2") (pinfunction "2_2") (pintype "passive"))
      (node (ref "R66") (pin "2") (pinfunction "2_2") (pintype "passive"))
      (node (ref "U10") (pin "10") (pinfunction "BIAS_10") (pintype "power_in"))
      (node (ref "U10") (pin "11") (pinfunction "EN_11") (pintype "input"))
      (node (ref "U10") (pin "5") (pinfunction "IN_5") (pintype "power_in"))
      (node (ref "U10") (pin "6") (pinfunction "IN_6") (pintype "power_in"))
      (node (ref "U10") (pin "7") (pinfunction "IN_7") (pintype "power_in"))
      (node (ref "U10") (pin "8") (pinfunction "IN_8") (pintype "power_in"))
      (node (ref "U3") (pin "10") (pinfunction "BIAS_10") (pintype "power_in"))
      (node (ref "U4") (pin "10") (pinfunction "BIAS_10") (pintype "power_in"))
      (node (ref "U4") (pin "11") (pinfunction "EN_11") (pintype "input"))
      (node (ref "U4") (pin "5") (pinfunction "IN_5") (pintype "power_in"))
      (node (ref "U4") (pin "6") (pinfunction "IN_6") (pintype "power_in"))
      (node (ref "U4") (pin "7") (pinfunction "IN_7") (pintype "power_in"))
      (node (ref "U4") (pin "8") (pinfunction "IN_8") (pintype "power_in"))
      (node (ref "U9") (pin "10") (pinfunction "BIAS_10") (pintype "power_in"))
    )
    (net (code "88") (name "GND") (class "Default")
      (node (ref "C124") (pin "1") (pinfunction "1_1") (pintype "passive"))
      (node (ref "C125") (pin "1") (pinfunction "1_1") (pintype "passive"))
      (node (ref "C126") (pin "1") (pinfunction "1_1") (pintype "passive"))
      (node (ref "C127") (pin "1") (pinfunction "1_1") (pintype "passive"))
      (node (ref "C128") (pin "1") (pinfunction "1_1") (pintype "passive"))
      (node (ref "C142") (pin "1") (pinfunction "1_1") (pintype "passive"))
      (node (ref "C143") (pin "1") (pinfunction "1_1") (pintype "passive"))
      (node (ref "C144") (pin "1") (pinfunction "1_1") (pintype "passive"))
      (node (ref "C145") (pin "1") (pinfunction "1_1") (pintype "passive"))
      (node (ref "C146") (pin "1") (pinfunction "1_1") (pintype "passive"))
      (node (ref "C147") (pin "1") (pinfunction "1_1") (pintype "passive"))
      (node (ref "C33") (pin "1") (pinfunction "1_1") (pintype "passive"))
      (node (ref "C34") (pin "1") (pinfunction "1_1") (pintype "passive"))
      (node (ref "C35") (pin "1") (pinfunction "1_1") (pintype "passive"))
      (node (ref "C36") (pin "1") (pinfunction "1_1") (pintype "passive"))
      (node (ref "C37") (pin "1") (pinfunction "1_1") (pintype "passive"))
      (node (ref "C38") (pin "1") (pinfunction "1_1") (pintype "passive"))
      (node (ref "C39") (pin "1") (pinfunction "1_1") (pintype "passive"))
      (node (ref "C40") (pin "1") (pinfunction "1_1") (pintype "passive"))
      (node (ref "C41") (pin "1") (pinfunction "1_1") (pintype "passive"))
      (node (ref "C42") (pin "1") (pinfunction "1_1") (pintype "passive"))
      (node (ref "C43") (pin "1") (pinfunction "1_1") (pintype "passive"))
      (node (ref "C44") (pin "1") (pinfunction "1_1") (pintype "passive"))
      (node (ref "C73") (pin "1") (pinfunction "1_1") (pintype "passive"))
      (node (ref "J1") (pin "AG1") (pinfunction "AG1_AG1") (pintype "power_in"))
      (node (ref "J1") (pin "AG10") (pinfunction "AG10_AG10") (pintype "power_in"))
      (node (ref "J1") (pin "AG11") (pinfunction "AG11_AG11") (pintype "power_in"))
      (node (ref "J1") (pin "AG12") (pinfunction "AG12_AG12") (pintype "power_in"))
      (node (ref "J1") (pin "AG13") (pinfunction "AG13_AG13") (pintype "power_in"))
      (node (ref "J1") (pin "AG14") (pinfunction "AG14_AG14") (pintype "power_in"))
      (node (ref "J1") (pin "AG15") (pinfunction "AG15_AG15") (pintype "power_in"))
      (node (ref "J1") (pin "AG16") (pinfunction "AG16_AG16") (pintype "power_in"))
      (node (ref "J1") (pin "AG17") (pinfunction "AG17_AG17") (pintype "power_in"))
      (node (ref "J1") (pin "AG18") (pinfunction "AG18_AG18") (pintype "power_in"))
      (node (ref "J1") (pin "AG19") (pinfunction "AG19_AG19") (pintype "power_in"))
      (node (ref "J1") (pin "AG2") (pinfunction "AG2_AG2") (pintype "power_in"))
      (node (ref "J1") (pin "AG20") (pinfunction "AG20_AG20") (pintype "power_in"))
      (node (ref "J1") (pin "AG3") (pinfunction "AG3_AG3") (pintype "power_in"))
      (node (ref "J1") (pin "AG4") (pinfunction "AG4_AG4") (pintype "power_in"))
      (node (ref "J1") (pin "AG5") (pinfunction "AG5_AG5") (pintype "power_in"))
      (node (ref "J1") (pin "AG6") (pinfunction "AG6_AG6") (pintype "power_in"))
      (node (ref "J1") (pin "AG7") (pinfunction "AG7_AG7") (pintype "power_in"))
      (node (ref "J1") (pin "AG8") (pinfunction "AG8_AG8") (pintype "power_in"))
      (node (ref "J1") (pin "AG9") (pinfunction "AG9_AG9") (pintype "power_in"))
      (node (ref "J1") (pin "AGND") (pinfunction "AGND_AGND") (pintype "power_in"))
      (node (ref "J1") (pin "BG1") (pinfunction "BG1_BG1") (pintype "power_in"))
      (node (ref "J1") (pin "BG10") (pinfunction "BG10_BG10") (pintype "power_in"))
      (node (ref "J1") (pin "BG11") (pinfunction "BG11_BG11") (pintype "power_in"))
      (node (ref "J1") (pin "BG12") (pinfunction "BG12_BG12") (pintype "power_in"))
      (node (ref "J1") (pin "BG13") (pinfunction "BG13_BG13") (pintype "power_in"))
      (node (ref "J1") (pin "BG14") (pinfunction "BG14_BG14") (pintype "power_in"))
      (node (ref "J1") (pin "BG15") (pinfunction "BG15_BG15") (pintype "power_in"))
      (node (ref "J1") (pin "BG16") (pinfunction "BG16_BG16") (pintype "power_in"))
      (node (ref "J1") (pin "BG17") (pinfunction "BG17_BG17") (pintype "power_in"))
      (node (ref "J1") (pin "BG18") (pinfunction "BG18_BG18") (pintype "power_in"))
      (node (ref "J1") (pin "BG19") (pinfunction "BG19_BG19") (pintype "power_in"))
      (node (ref "J1") (pin "BG2") (pinfunction "BG2_BG2") (pintype "power_in"))
      (node (ref "J1") (pin "BG20") (pinfunction "BG20_BG20") (pintype "power_in"))
      (node (ref "J1") (pin "BG3") (pinfunction "BG3_BG3") (pintype "power_in"))
      (node (ref "J1") (pin "BG4") (pinfunction "BG4_BG4") (pintype "power_in"))
      (node (ref "J1") (pin "BG5") (pinfunction "BG5_BG5") (pintype "power_in"))
      (node (ref "J1") (pin "BG6") (pinfunction "BG6_BG6") (pintype "power_in"))
      (node (ref "J1") (pin "BG7") (pinfunction "BG7_BG7") (pintype "power_in"))
      (node (ref "J1") (pin "BG8") (pinfunction "BG8_BG8") (pintype "power_in"))
      (node (ref "J1") (pin "BG9") (pinfunction "BG9_BG9") (pintype "power_in"))
      (node (ref "J1") (pin "BGND") (pinfunction "BGND_BGND") (pintype "power_in"))
      (node (ref "J1") (pin "C1") (pinfunction "C1_C1") (pintype "bidirectional"))
      (node (ref "J1") (pin "C10") (pinfunction "C10_C10") (pintype "bidirectional"))
      (node (ref "J1") (pin "C13") (pinfunction "C13_C13") (pintype "bidirectional"))
      (node (ref "J1") (pin "C14") (pinfunction "C14_C14") (pintype "bidirectional"))
      (node (ref "J1") (pin "C2") (pinfunction "C2_C2") (pintype "bidirectional"))
      (node (ref "J1") (pin "C25") (pinfunction "C25_C25") (pintype "bidirectional"))
      (node (ref "J1") (pin "C26") (pinfunction "C26_C26") (pintype "bidirectional"))
      (node (ref "J1") (pin "C29") (pinfunction "C29_C29") (pintype "bidirectional"))
      (node (ref "J1") (pin "C30") (pinfunction "C30_C30") (pintype "bidirectional"))
      (node (ref "J1") (pin "C5") (pinfunction "C5_C5") (pintype "bidirectional"))
      (node (ref "J1") (pin "C6") (pinfunction "C6_C6") (pintype "bidirectional"))
      (node (ref "J1") (pin "C9") (pinfunction "C9_C9") (pintype "bidirectional"))
      (node (ref "J1") (pin "CG1") (pinfunction "CG1_CG1") (pintype "power_in"))
      (node (ref "J1") (pin "CG10") (pinfunction "CG10_CG10") (pintype "power_in"))
      (node (ref "J1") (pin "CG11") (pinfunction "CG11_CG11") (pintype "power_in"))
      (node (ref "J1") (pin "CG12") (pinfunction "CG12_CG12") (pintype "power_in"))
      (node (ref "J1") (pin "CG13") (pinfunction "CG13_CG13") (pintype "power_in"))
      (node (ref "J1") (pin "CG14") (pinfunction "CG14_CG14") (pintype "power_in"))
      (node (ref "J1") (pin "CG15") (pinfunction "CG15_CG15") (pintype "power_in"))
      (node (ref "J1") (pin "CG16") (pinfunction "CG16_CG16") (pintype "power_in"))
      (node (ref "J1") (pin "CG17") (pinfunction "CG17_CG17") (pintype "power_in"))
      (node (ref "J1") (pin "CG18") (pinfunction "CG18_CG18") (pintype "power_in"))
      (node (ref "J1") (pin "CG19") (pinfunction "CG19_CG19") (pintype "power_in"))
      (node (ref "J1") (pin "CG2") (pinfunction "CG2_CG2") (pintype "power_in"))
      (node (ref "J1") (pin "CG20") (pinfunction "CG20_CG20") (pintype "power_in"))
      (node (ref "J1") (pin "CG3") (pinfunction "CG3_CG3") (pintype "power_in"))
      (node (ref "J1") (pin "CG4") (pinfunction "CG4_CG4") (pintype "power_in"))
      (node (ref "J1") (pin "CG5") (pinfunction "CG5_CG5") (pintype "power_in"))
      (node (ref "J1") (pin "CG6") (pinfunction "CG6_CG6") (pintype "power_in"))
      (node (ref "J1") (pin "CG7") (pinfunction "CG7_CG7") (pintype "power_in"))
      (node (ref "J1") (pin "CG8") (pinfunction "CG8_CG8") (pintype "power_in"))
      (node (ref "J1") (pin "CG9") (pinfunction "CG9_CG9") (pintype "power_in"))
      (node (ref "J1") (pin "CGND") (pinfunction "CGND_CGND") (pintype "power_in"))
      (node (ref "J1") (pin "D1") (pinfunction "D1_D1") (pintype "bidirectional"))
      (node (ref "J1") (pin "D10") (pinfunction "D10_D10") (pintype "bidirectional"))
      (node (ref "J1") (pin "D13") (pinfunction "D13_D13") (pintype "bidirectional"))
      (node (ref "J1") (pin "D14") (pinfunction "D14_D14") (pintype "bidirectional"))
      (node (ref "J1") (pin "D2") (pinfunction "D2_D2") (pintype "bidirectional"))
      (node (ref "J1") (pin "D25") (pinfunction "D25_D25") (pintype "bidirectional"))
      (node (ref "J1") (pin "D26") (pinfunction "D26_D26") (pintype "bidirectional"))
      (node (ref "J1") (pin "D29") (pinfunction "D29_D29") (pintype "bidirectional"))
      (node (ref "J1") (pin "D30") (pinfunction "D30_D30") (pintype "bidirectional"))
      (node (ref "J1") (pin "D5") (pinfunction "D5_D5") (pintype "bidirectional"))
      (node (ref "J1") (pin "D6") (pinfunction "D6_D6") (pintype "bidirectional"))
      (node (ref "J1") (pin "D9") (pinfunction "D9_D9") (pintype "bidirectional"))
      (node (ref "J1") (pin "DG1") (pinfunction "DG1_DG1") (pintype "power_in"))
      (node (ref "J1") (pin "DG10") (pinfunction "DG10_DG10") (pintype "power_in"))
      (node (ref "J1") (pin "DG11") (pinfunction "DG11_DG11") (pintype "power_in"))
      (node (ref "J1") (pin "DG12") (pinfunction "DG12_DG12") (pintype "power_in"))
      (node (ref "J1") (pin "DG13") (pinfunction "DG13_DG13") (pintype "power_in"))
      (node (ref "J1") (pin "DG14") (pinfunction "DG14_DG14") (pintype "power_in"))
      (node (ref "J1") (pin "DG15") (pinfunction "DG15_DG15") (pintype "power_in"))
      (node (ref "J1") (pin "DG16") (pinfunction "DG16_DG16") (pintype "power_in"))
      (node (ref "J1") (pin "DG17") (pinfunction "DG17_DG17") (pintype "power_in"))
      (node (ref "J1") (pin "DG18") (pinfunction "DG18_DG18") (pintype "power_in"))
      (node (ref "J1") (pin "DG19") (pinfunction "DG19_DG19") (pintype "power_in"))
      (node (ref "J1") (pin "DG2") (pinfunction "DG2_DG2") (pintype "power_in"))
      (node (ref "J1") (pin "DG20") (pinfunction "DG20_DG20") (pintype "power_in"))
      (node (ref "J1") (pin "DG3") (pinfunction "DG3_DG3") (pintype "power_in"))
      (node (ref "J1") (pin "DG4") (pinfunction "DG4_DG4") (pintype "power_in"))
      (node (ref "J1") (pin "DG5") (pinfunction "DG5_DG5") (pintype "power_in"))
      (node (ref "J1") (pin "DG6") (pinfunction "DG6_DG6") (pintype "power_in"))
      (node (ref "J1") (pin "DG7") (pinfunction "DG7_DG7") (pintype "power_in"))
      (node (ref "J1") (pin "DG8") (pinfunction "DG8_DG8") (pintype "power_in"))
      (node (ref "J1") (pin "DG9") (pinfunction "DG9_DG9") (pintype "power_in"))
      (node (ref "J1") (pin "DGND") (pinfunction "DGND_DGND") (pintype "power_in"))
      (node (ref "P6") (pin "11") (pinfunction "11_11") (pintype "passive"))
      (node (ref "P6") (pin "12") (pinfunction "12_12") (pintype "passive"))
      (node (ref "P6") (pin "3") (pinfunction "3_3") (pintype "passive"))
      (node (ref "P6") (pin "4") (pinfunction "4_4") (pintype "passive"))
      (node (ref "P6") (pin "7") (pinfunction "7_7") (pintype "passive"))
      (node (ref "P6") (pin "8") (pinfunction "8_8") (pintype "passive"))
      (node (ref "R10") (pin "1") (pinfunction "1_1") (pintype "passive"))
      (node (ref "R11") (pin "1") (pinfunction "1_1") (pintype "passive"))
      (node (ref "R3") (pin "1") (pinfunction "1_1") (pintype "passive"))
      (node (ref "R46") (pin "1") (pinfunction "1_1") (pintype "passive"))
      (node (ref "R6") (pin "1") (pinfunction "1_1") (pintype "passive"))
      (node (ref "R68") (pin "1") (pinfunction "1_1") (pintype "passive"))
      (node (ref "R9") (pin "1") (pinfunction "1_1") (pintype "passive"))
      (node (ref "U10") (pin "12") (pinfunction "GND_12") (pintype "power_in"))
      (node (ref "U10") (pin "21") (pinfunction "TH_GND_21") (pintype "power_in"))
      (node (ref "U3") (pin "12") (pinfunction "GND_12") (pintype "power_in"))
      (node (ref "U3") (pin "21") (pinfunction "TH_GND_21") (pintype "power_in"))
      (node (ref "U4") (pin "12") (pinfunction "GND_12") (pintype "power_in"))
      (node (ref "U4") (pin "21") (pinfunction "TH_GND_21") (pintype "power_in"))
      (node (ref "U9") (pin "12") (pinfunction "GND_12") (pintype "power_in"))
      (node (ref "U9") (pin "21") (pinfunction "TH_GND_21") (pintype "power_in"))
    )
    (net (code "89") (name "Net-(U3-FB)") (class "Default")
      (node (ref "R2") (pin "1") (pinfunction "1_1") (pintype "passive"))
      (node (ref "R3") (pin "2") (pinfunction "2_2") (pintype "passive"))
      (node (ref "U3") (pin "16") (pinfunction "FB_16") (pintype "input"))
    )
    (net (code "90") (name "Net-(U3-PG)") (class "Default")
      (node (ref "R1") (pin "1") (pinfunction "1_1") (pintype "passive"))
      (node (ref "TP1") (pin "1") (pinfunction "1_1") (pintype "passive"))
      (node (ref "U3") (pin "9") (pinfunction "PG_9") (pintype "output"))
    )
    (net (code "91") (name "Net-(U3-SS)") (class "Default")
      (node (ref "C38") (pin "2") (pinfunction "2_2") (pintype "passive"))
      (node (ref "U3") (pin "15") (pinfunction "SS_15") (pintype "passive"))
    )
    (net (code "92") (name "Net-(U4-FB)") (class "Default")
      (node (ref "R5") (pin "1") (pinfunction "1_1") (pintype "passive"))
      (node (ref "R6") (pin "2") (pinfunction "2_2") (pintype "passive"))
      (node (ref "U4") (pin "16") (pinfunction "FB_16") (pintype "input"))
    )
    (net (code "93") (name "Net-(U4-PG)") (class "Default")
      (node (ref "R4") (pin "1") (pinfunction "1_1") (pintype "passive"))
      (node (ref "TP2") (pin "1") (pinfunction "1_1") (pintype "passive"))
      (node (ref "U4") (pin "9") (pinfunction "PG_9") (pintype "output"))
    )
    (net (code "94") (name "Net-(U4-SS)") (class "Default")
      (node (ref "C44") (pin "2") (pinfunction "2_2") (pintype "passive"))
      (node (ref "U4") (pin "15") (pinfunction "SS_15") (pintype "passive"))
    )
    (net (code "95") (name "Net-(U9-FB)") (class "Default")
      (node (ref "R45") (pin "1") (pinfunction "1_1") (pintype "passive"))
      (node (ref "R46") (pin "2") (pinfunction "2_2") (pintype "passive"))
      (node (ref "U9") (pin "16") (pinfunction "FB_16") (pintype "input"))
    )
    (net (code "96") (name "Net-(U9-PG)") (class "Default")
      (node (ref "R44") (pin "1") (pinfunction "1_1") (pintype "passive"))
      (node (ref "TP4") (pin "1") (pinfunction "1_1") (pintype "passive"))
      (node (ref "U9") (pin "9") (pinfunction "PG_9") (pintype "output"))
    )
    (net (code "97") (name "Net-(U9-SS)") (class "Default")
      (node (ref "C128") (pin "2") (pinfunction "2_2") (pintype "passive"))
      (node (ref "U9") (pin "15") (pinfunction "SS_15") (pintype "passive"))
    )
    (net (code "98") (name "Net-(U10-FB)") (class "Default")
      (node (ref "R67") (pin "1") (pinfunction "1_1") (pintype "passive"))
      (node (ref "R68") (pin "2") (pinfunction "2_2") (pintype "passive"))
      (node (ref "U10") (pin "16") (pinfunction "FB_16") (pintype "input"))
    )
    (net (code "99") (name "Net-(U10-PG)") (class "Default")
      (node (ref "R66") (pin "1") (pinfunction "1_1") (pintype "passive"))
      (node (ref "TP5") (pin "1") (pinfunction "1_1") (pintype "passive"))
      (node (ref "U10") (pin "9") (pinfunction "PG_9") (pintype "output"))
    )
    (net (code "100") (name "Net-(U10-SS)") (class "Default")
      (node (ref "C147") (pin "2") (pinfunction "2_2") (pintype "passive"))
      (node (ref "U10") (pin "15") (pinfunction "SS_15") (pintype "passive"))
    )
    (net (code "101") (name "unconnected-(J1-PadC22)") (class "Default")
      (node (ref "J1") (pin "C22") (pinfunction "C22_C22") (pintype "bidirectional+no_connect"))
    )
    (net (code "102") (name "unconnected-(J1-PadC23)") (class "Default")
      (node (ref "J1") (pin "C23") (pinfunction "C23_C23") (pintype "bidirectional+no_connect"))
    )
    (net (code "103") (name "unconnected-(J1-PadC24)") (class "Default")
      (node (ref "J1") (pin "C24") (pinfunction "C24_C24") (pintype "bidirectional+no_connect"))
    )
    (net (code "104") (name "unconnected-(J1-PadD17)") (class "Default")
      (node (ref "J1") (pin "D17") (pinfunction "D17_D17") (pintype "bidirectional"))
    )
    (net (code "105") (name "unconnected-(J1-PadD18)") (class "Default")
      (node (ref "J1") (pin "D18") (pinfunction "D18_D18") (pintype "bidirectional+no_connect"))
    )
    (net (code "106") (name "unconnected-(J1-PadD19)") (class "Default")
      (node (ref "J1") (pin "D19") (pinfunction "D19_D19") (pintype "bidirectional+no_connect"))
    )
    (net (code "107") (name "unconnected-(J1-PadD20)") (class "Default")
      (node (ref "J1") (pin "D20") (pinfunction "D20_D20") (pintype "bidirectional+no_connect"))
    )
    (net (code "108") (name "unconnected-(J1-PadD21)") (class "Default")
      (node (ref "J1") (pin "D21") (pinfunction "D21_D21") (pintype "bidirectional+no_connect"))
    )
    (net (code "109") (name "unconnected-(J1-PadD22)") (class "Default")
      (node (ref "J1") (pin "D22") (pinfunction "D22_D22") (pintype "bidirectional+no_connect"))
    )
    (net (code "110") (name "unconnected-(J1-PadD23)") (class "Default")
      (node (ref "J1") (pin "D23") (pinfunction "D23_D23") (pintype "bidirectional+no_connect"))
    )
    (net (code "111") (name "unconnected-(J1-PadD24)") (class "Default")
      (node (ref "J1") (pin "D24") (pinfunction "D24_D24") (pintype "bidirectional+no_connect"))
    )
    (net (code "112") (name "unconnected-(U3-NC-Pad2)") (class "Default")
      (node (ref "U3") (pin "2") (pinfunction "NC_2") (pintype "passive+no_connect"))
    )
    (net (code "113") (name "unconnected-(U3-NC-Pad3)") (class "Default")
      (node (ref "U3") (pin "3") (pinfunction "NC_3") (pintype "passive+no_connect"))
    )
    (net (code "114") (name "unconnected-(U3-NC-Pad4)") (class "Default")
      (node (ref "U3") (pin "4") (pinfunction "NC_4") (pintype "passive+no_connect"))
    )
    (net (code "115") (name "unconnected-(U3-NC-Pad13)") (class "Default")
      (node (ref "U3") (pin "13") (pinfunction "NC_13") (pintype "passive+no_connect"))
    )
    (net (code "116") (name "unconnected-(U3-NC-Pad14)") (class "Default")
      (node (ref "U3") (pin "14") (pinfunction "NC_14") (pintype "passive+no_connect"))
    )
    (net (code "117") (name "unconnected-(U3-NC-Pad17)") (class "Default")
      (node (ref "U3") (pin "17") (pinfunction "NC_17") (pintype "passive+no_connect"))
    )
    (net (code "118") (name "unconnected-(U4-NC-Pad2)") (class "Default")
      (node (ref "U4") (pin "2") (pinfunction "NC_2") (pintype "passive+no_connect"))
    )
    (net (code "119") (name "unconnected-(U4-NC-Pad3)") (class "Default")
      (node (ref "U4") (pin "3") (pinfunction "NC_3") (pintype "passive+no_connect"))
    )
    (net (code "120") (name "unconnected-(U4-NC-Pad4)") (class "Default")
      (node (ref "U4") (pin "4") (pinfunction "NC_4") (pintype "passive+no_connect"))
    )
    (net (code "121") (name "unconnected-(U4-NC-Pad13)") (class "Default")
      (node (ref "U4") (pin "13") (pinfunction "NC_13") (pintype "passive+no_connect"))
    )
    (net (code "122") (name "unconnected-(U4-NC-Pad14)") (class "Default")
      (node (ref "U4") (pin "14") (pinfunction "NC_14") (pintype "passive+no_connect"))
    )
    (net (code "123") (name "unconnected-(U4-NC-Pad17)") (class "Default")
      (node (ref "U4") (pin "17") (pinfunction "NC_17") (pintype "passive+no_connect"))
    )
    (net (code "124") (name "unconnected-(U9-NC-Pad2)") (class "Default")
      (node (ref "U9") (pin "2") (pinfunction "NC_2") (pintype "passive+no_connect"))
    )
    (net (code "125") (name "unconnected-(U9-NC-Pad3)") (class "Default")
      (node (ref "U9") (pin "3") (pinfunction "NC_3") (pintype "passive+no_connect"))
    )
    (net (code "126") (name "unconnected-(U9-NC-Pad4)") (class "Default")
      (node (ref "U9") (pin "4") (pinfunction "NC_4") (pintype "passive+no_connect"))
    )
    (net (code "127") (name "unconnected-(U9-NC-Pad13)") (class "Default")
      (node (ref "U9") (pin "13") (pinfunction "NC_13") (pintype "passive+no_connect"))
    )
    (net (code "128") (name "unconnected-(U9-NC-Pad14)") (class "Default")
      (node (ref "U9") (pin "14") (pinfunction "NC_14") (pintype "passive+no_connect"))
    )
    (net (code "129") (name "unconnected-(U9-NC-Pad17)") (class "Default")
      (node (ref "U9") (pin "17") (pinfunction "NC_17") (pintype "passive+no_connect"))
    )
    (net (code "130") (name "unconnected-(U10-NC-Pad2)") (class "Default")
      (node (ref "U10") (pin "2") (pinfunction "NC_2") (pintype "passive+no_connect"))
    )
    (net (code "131") (name "unconnected-(U10-NC-Pad3)") (class "Default")
      (node (ref "U10") (pin "3") (pinfunction "NC_3") (pintype "passive+no_connect"))
    )
    (net (code "132") (name "unconnected-(U10-NC-Pad4)") (class "Default")
      (node (ref "U10") (pin "4") (pinfunction "NC_4") (pintype "passive+no_connect"))
    )
    (net (code "133") (name "unconnected-(U10-NC-Pad13)") (class "Default")
      (node (ref "U10") (pin "13") (pinfunction "NC_13") (pintype "passive+no_connect"))
    )
    (net (code "134") (name "unconnected-(U10-NC-Pad14)") (class "Default")
      (node (ref "U10") (pin "14") (pinfunction "NC_14") (pintype "passive+no_connect"))
    )
    (net (code "135") (name "unconnected-(U10-NC-Pad17)") (class "Default")
      (node (ref "U10") (pin "17") (pinfunction "NC_17") (pintype "passive+no_connect"))
    )
  )
)
